# qstp_q4.net
KiCad netlist of a schematic drawn in EAGLE
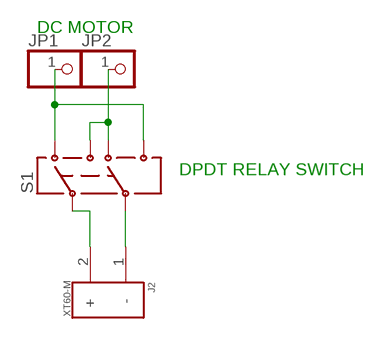
[diagram p0: schematic, sheet 1]

(export (version "E")
  (design (tool "Eeschema 10.0.6"))
  (components
    (comp (ref "J2")
      (value "XT60-M")
      (footprint "eagle-import:AMASS_XT60-M")
      (fields (field (name "MF") "AMASS"))
      (libsource (lib "eagle-import") (part "XT60-M"))
    )
    (comp (ref "JP1")
      (value "PINHD-1X1")
      (footprint "eagle-import:1X01")
      (libsource (lib "eagle-import") (part "PINHD-1X1"))
    )
    (comp (ref "JP2")
      (value "PINHD-1X1")
      (footprint "eagle-import:1X01")
      (libsource (lib "eagle-import") (part "PINHD-1X1"))
    )
    (comp (ref "S1")
      (value "SWITCH-DPDTEG2211")
      (footprint "eagle-import:EG2211")
      (libsource (lib "eagle-import") (part "SWITCH-DPDTEG2211"))
    )
  )
  (nets
    (net (code "1") (name "Net-(J2-+)") (class "Default")
      (node (ref "J2") (pin "2") (pinfunction "+_2") (pintype "passive"))
      (node (ref "S1") (pin "P1") (pinfunction "2_P1") (pintype "bidirectional"))
    )
    (net (code "2") (name "Net-(J2--)") (class "Default")
      (node (ref "J2") (pin "1") (pinfunction "-_1") (pintype "passive"))
      (node (ref "S1") (pin "P2") (pinfunction "5_P2") (pintype "bidirectional"))
    )
    (net (code "3") (name "Net-(S1-1)") (class "Default")
      (node (ref "JP1") (pin "1") (pinfunction "1_1") (pintype "passive"))
      (node (ref "S1") (pin "P1-TA") (pinfunction "1_P1-TA") (pintype "bidirectional"))
      (node (ref "S1") (pin "P2-TB") (pinfunction "6_P2-TB") (pintype "bidirectional"))
    )
    (net (code "4") (name "Net-(S1-3)") (class "Default")
      (node (ref "JP2") (pin "1") (pinfunction "1_1") (pintype "passive"))
      (node (ref "S1") (pin "P1-TB") (pinfunction "3_P1-TB") (pintype "bidirectional"))
      (node (ref "S1") (pin "P2-TA") (pinfunction "4_P2-TA") (pintype "bidirectional"))
    )
  )
)
